# Deck_SchV1_1.net
KiCad netlist of a schematic drawn in Altium Designer
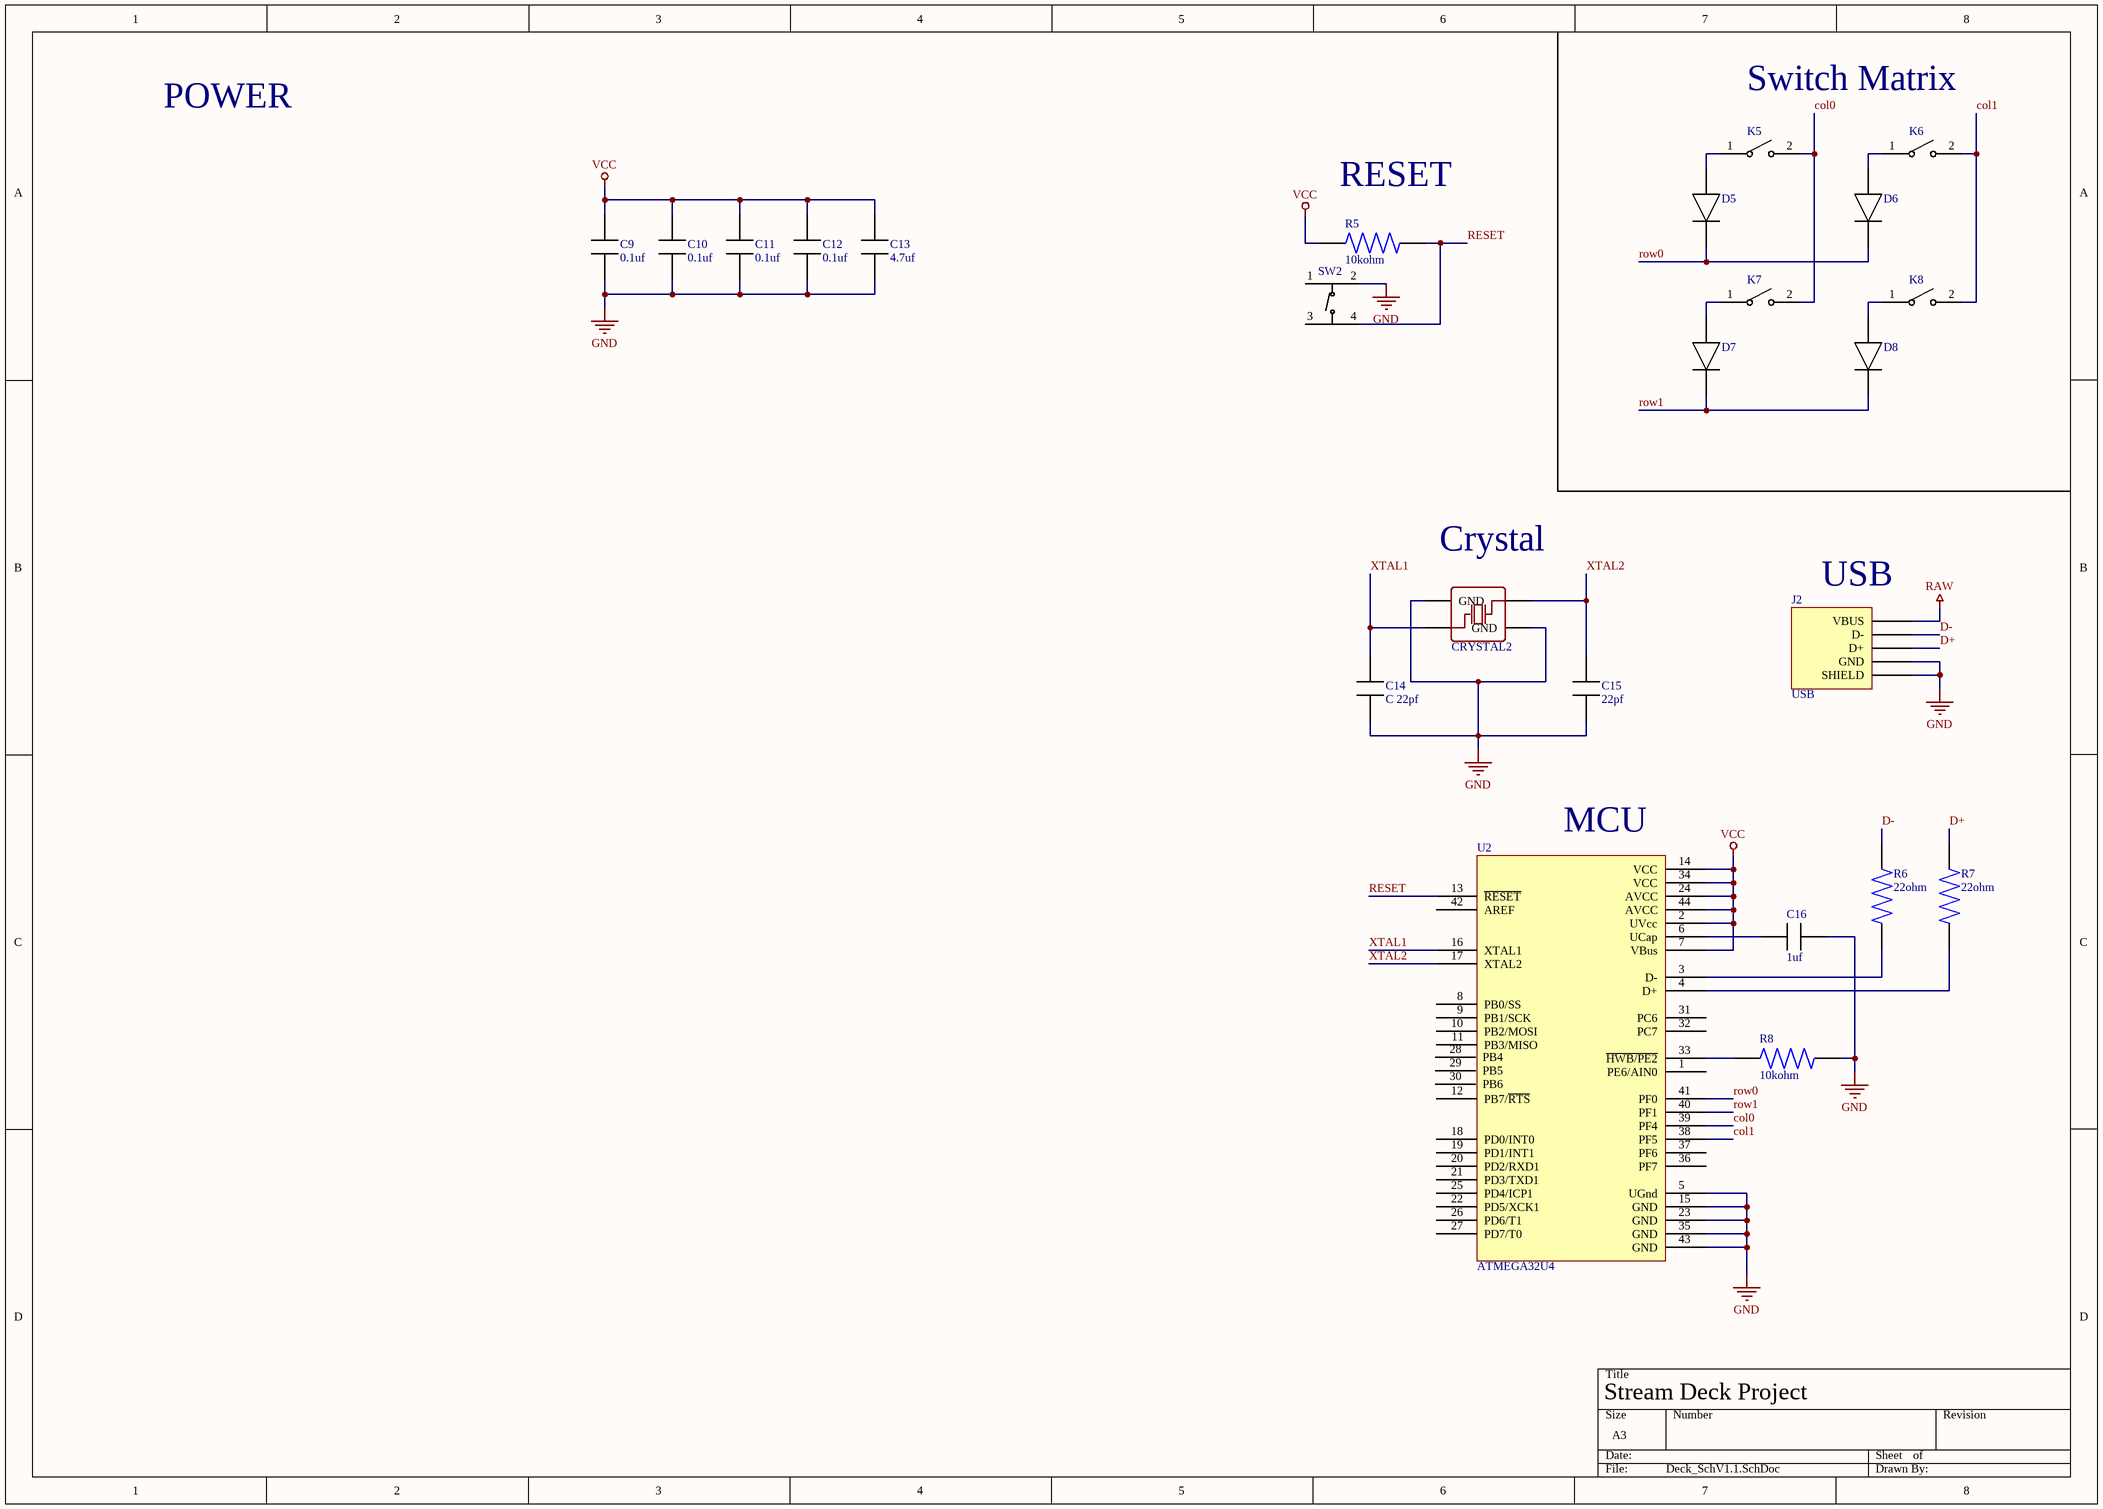
[diagram p0: Deck_SchV1.1.SchDoc]

(export (version "E")
  (design (tool "Eeschema 10.0.6"))
  (components
    (comp (ref "C9")
      (value "0.1uf")
      (footprint "C0805")
      (fields
        (field (name "MANUFACTURER") "Yageo")
        (field (name "MANUFACTURER PART NUMBER") "CC0805ZRY5V9BB104")
        (field (name "TOLERANCE") "80%")
      )
      (libsource (lib "Deck_SchlibV2") (part "CC0805ZRY5V9BB104"))
    )
    (comp (ref "C10")
      (value "0.1uf")
      (footprint "C0805")
      (fields
        (field (name "MANUFACTURER") "Yageo")
        (field (name "MANUFACTURER PART NUMBER") "CC0805ZRY5V9BB104")
        (field (name "TOLERANCE") "80%")
      )
      (libsource (lib "Deck_SchlibV2") (part "CC0805ZRY5V9BB104"))
    )
    (comp (ref "C11")
      (value "0.1uf")
      (footprint "C0805")
      (fields
        (field (name "MANUFACTURER") "Yageo")
        (field (name "MANUFACTURER PART NUMBER") "CC0805ZRY5V9BB104")
        (field (name "TOLERANCE") "80%")
      )
      (libsource (lib "Deck_SchlibV2") (part "CC0805ZRY5V9BB104"))
    )
    (comp (ref "C12")
      (value "0.1uf")
      (footprint "C0805")
      (fields
        (field (name "MANUFACTURER") "Yageo")
        (field (name "MANUFACTURER PART NUMBER") "CC0805ZRY5V9BB104")
        (field (name "TOLERANCE") "80%")
      )
      (libsource (lib "Deck_SchlibV2") (part "CC0805ZRY5V9BB104"))
    )
    (comp (ref "C13")
      (value "4.7uf")
      (footprint "C0805")
      (fields
        (field (name "MANUFACTURER") "Samsung")
        (field (name "MANUFACTURER PART NUMBER") "CL21A475KAQNNNE")
        (field (name "TOLERANCE") "10%")
      )
      (libsource (lib "Deck_SchlibV2") (part "CL21A475KAQNNNE"))
    )
    (comp (ref "C14")
      (value "C 22pf")
      (footprint "C0805")
      (description "Cap Ceramic 22pF 50V C0G 5% SMD 0805 125C T/R")
      (fields
        (field (name "MANUFACTURER") "Samsung")
        (field (name "MANUFACTURER PART NUMBER") "CL21C220JBANNNC")
      )
      (libsource (lib "Deck_SchlibV2") (part "CL21C220JBANNNC"))
    )
    (comp (ref "C15")
      (value "22pf")
      (footprint "C0805")
      (description "Cap Ceramic 22pF 50V C0G 5% SMD 0805 125C T/R")
      (fields
        (field (name "MANUFACTURER") "Samsung")
        (field (name "MANUFACTURER PART NUMBER") "CL21C220JBANNNC")
      )
      (libsource (lib "Deck_SchlibV2") (part "CL21C220JBANNNC"))
    )
    (comp (ref "C16")
      (value "1uf")
      (footprint "C0805")
      (fields
        (field (name "MANUFACTURER") "Samsung")
        (field (name "MANUFACTURER PART NUMBER") "CL21B105KBFNNNE")
        (field (name "TOLERANCE") "10%")
      )
      (libsource (lib "Deck_SchlibV2") (part "CL21B105KBFNNNE"))
    )
    (comp (ref "CRYSTAL2")
      (value "Crystal")
      (footprint "CRYSTAL-SMD_4P-L3.2-W2.5-BL")
      (fields (field (name "MANUFACTURER") "Seiko") (field (name "MANUFACTURER PART NUMBER") "X1E0000210264"))
      (libsource (lib "Deck_SchlibV2") (part "X1E0000210264"))
    )
    (comp (ref "D5")
      (value "Diode")
      (footprint "SOD-123_L2.8-W1.8-LS3.7-RD")
      (description "MICRO COMMERCIAL COMPONENTS - 1N4148W-TP - SWITCHING DIODE, 150mA, 100V, SOD123, FU")
      (fields (field (name "MANUFACTURER") "MCC") (field (name "MANUFACTURER PART NUMBER") "1N4148W-TP"))
      (libsource (lib "Deck_SchlibV2") (part "1N4148W-TP"))
    )
    (comp (ref "D6")
      (value "Diode")
      (footprint "SOD-123_L2.8-W1.8-LS3.7-RD")
      (description "MICRO COMMERCIAL COMPONENTS - 1N4148W-TP - SWITCHING DIODE, 150mA, 100V, SOD123, FU")
      (fields (field (name "MANUFACTURER") "MCC") (field (name "MANUFACTURER PART NUMBER") "1N4148W-TP"))
      (libsource (lib "Deck_SchlibV2") (part "1N4148W-TP"))
    )
    (comp (ref "D7")
      (value "Diode")
      (footprint "SOD-123_L2.8-W1.8-LS3.7-RD")
      (description "MICRO COMMERCIAL COMPONENTS - 1N4148W-TP - SWITCHING DIODE, 150mA, 100V, SOD123, FU")
      (fields (field (name "MANUFACTURER") "MCC") (field (name "MANUFACTURER PART NUMBER") "1N4148W-TP"))
      (libsource (lib "Deck_SchlibV2") (part "1N4148W-TP"))
    )
    (comp (ref "D8")
      (value "Diode")
      (footprint "SOD-123_L2.8-W1.8-LS3.7-RD")
      (description "MICRO COMMERCIAL COMPONENTS - 1N4148W-TP - SWITCHING DIODE, 150mA, 100V, SOD123, FU")
      (fields (field (name "MANUFACTURER") "MCC") (field (name "MANUFACTURER PART NUMBER") "1N4148W-TP"))
      (libsource (lib "Deck_SchlibV2") (part "1N4148W-TP"))
    )
    (comp (ref "J2")
      (value "USB")
      (footprint "USB")
      (description "Conn Mini USB 2.0 Type B RCP 5 POS 0.8mm Solder RA SMD 5 Terminal 1 Port Embossed T/R")
      (fields
        (field (name "MANUFACTURER") "Hirose")
        (field (name "MANUFACTURER PART NUMBER") "UX60SC-MB-5S8")
      )
      (libsource (lib "Deck_SchlibV2") (part "UX60SC-MB-5S8"))
    )
    (comp (ref "K5")
      (value "Switch")
      (footprint "Mx_Alps_100")
      (libsource (lib "Deck_SchlibV2") (part "Keyboard Switch"))
    )
    (comp (ref "K6")
      (value "Switch")
      (footprint "Mx_Alps_100")
      (libsource (lib "Deck_SchlibV2") (part "Keyboard Switch"))
    )
    (comp (ref "K7")
      (value "Switch")
      (footprint "Mx_Alps_100")
      (libsource (lib "Deck_SchlibV2") (part "Keyboard Switch"))
    )
    (comp (ref "K8")
      (value "Switch")
      (footprint "Mx_Alps_100")
      (libsource (lib "Deck_SchlibV2") (part "Keyboard Switch"))
    )
    (comp (ref "R5")
      (value "10kohm")
      (footprint "R0805")
      (fields
        (field (name "MANUFACTURER") "Uniroyal")
        (field (name "MANUFACTURER PART NUMBER") "0805W8F1002T5E")
      )
      (libsource (lib "Deck_SchlibV2") (part "0805W8F1002T5E"))
    )
    (comp (ref "R6")
      (value "22ohm")
      (footprint "R0805")
      (fields
        (field (name "MANUFACTURER") "Uniroyal")
        (field (name "MANUFACTURER PART NUMBER") "0805W8F220JT5E")
      )
      (libsource (lib "Deck_SchlibV2") (part "0805W8F220JT5E"))
    )
    (comp (ref "R7")
      (value "22ohm")
      (footprint "R0805")
      (fields
        (field (name "MANUFACTURER") "Uniroyal")
        (field (name "MANUFACTURER PART NUMBER") "0805W8F220JT5E")
      )
      (libsource (lib "Deck_SchlibV2") (part "0805W8F220JT5E"))
    )
    (comp (ref "R8")
      (value "10kohm")
      (footprint "R0805")
      (fields
        (field (name "MANUFACTURER") "Uniroyal")
        (field (name "MANUFACTURER PART NUMBER") "0805W8F1002T5E")
      )
      (libsource (lib "Deck_SchlibV2") (part "0805W8F1002T5E"))
    )
    (comp (ref "SW2")
      (value "Button")
      (footprint "SW-SMD_4P-L5.1-W5.1-P3.70-LS6.5-TL-2")
      (fields
        (field (name "MANUFACTURER") "XKB Connectivity")
        (field (name "MANUFACTURER PART NUMBER") "TS-1187A-B-A-B")
      )
      (libsource (lib "Deck_SchlibV2") (part "TS-1187A-B-A-B"))
    )
    (comp (ref "U2")
      (value "ATMEGA32U4")
      (footprint "ATMEGA32U2-AUR")
      (description "IC MCU 8BIT 32KB FLASH 32TQFP")
      (fields
        (field (name "MANUFACTURER") "Microchip / Atmel")
        (field (name "MANUFACTURER PART NUMBER") "ATMEGA32U2-AUR")
      )
      (libsource (lib "Deck_SchlibV2") (part "ATMEGA32U2-AUR"))
    )
  )
  (nets
    (net (code "1") (name "/D+") (class "Default")
      (node (ref "J2") (pin "3") (pinfunction "D+_3") (pintype "passive"))
      (node (ref "R7") (pin "57") (pinfunction "57_57") (pintype "passive"))
    )
    (net (code "2") (name "/D-") (class "Default")
      (node (ref "J2") (pin "2") (pinfunction "D-_2") (pintype "passive"))
      (node (ref "R6") (pin "57") (pinfunction "57_57") (pintype "passive"))
    )
    (net (code "3") (name "/RESET") (class "Default")
      (node (ref "R5") (pin "57") (pinfunction "57_57") (pintype "passive"))
      (node (ref "SW2") (pin "4") (pinfunction "D_4") (pintype "passive"))
      (node (ref "U2") (pin "13") (pinfunction "~{RESET}_13") (pintype "passive"))
    )
    (net (code "4") (name "/XTAL1") (class "Default")
      (node (ref "C14") (pin "54") (pinfunction "54_54") (pintype "passive"))
      (node (ref "CRYSTAL2") (pin "1") (pinfunction "OSC1_1") (pintype "passive"))
      (node (ref "U2") (pin "16") (pinfunction "XTAL1_16") (pintype "passive"))
    )
    (net (code "5") (name "/XTAL2") (class "Default")
      (node (ref "C15") (pin "54") (pinfunction "54_54") (pintype "passive"))
      (node (ref "CRYSTAL2") (pin "3") (pinfunction "OSC2_3") (pintype "passive"))
      (node (ref "U2") (pin "17") (pinfunction "XTAL2_17") (pintype "passive"))
    )
    (net (code "6") (name "/col0") (class "Default")
      (node (ref "K5") (pin "2") (pinfunction "2_2") (pintype "passive"))
      (node (ref "K7") (pin "2") (pinfunction "2_2") (pintype "passive"))
      (node (ref "U2") (pin "39") (pinfunction "PF4_39") (pintype "passive"))
    )
    (net (code "7") (name "/col1") (class "Default")
      (node (ref "K6") (pin "2") (pinfunction "2_2") (pintype "passive"))
      (node (ref "K8") (pin "2") (pinfunction "2_2") (pintype "passive"))
      (node (ref "U2") (pin "38") (pinfunction "PF5_38") (pintype "passive"))
    )
    (net (code "8") (name "/row0") (class "Default")
      (node (ref "D5") (pin "2") (pinfunction "-_2") (pintype "passive"))
      (node (ref "D6") (pin "2") (pinfunction "-_2") (pintype "passive"))
      (node (ref "U2") (pin "41") (pinfunction "PF0_41") (pintype "passive"))
    )
    (net (code "9") (name "/row1") (class "Default")
      (node (ref "D7") (pin "2") (pinfunction "-_2") (pintype "passive"))
      (node (ref "D8") (pin "2") (pinfunction "-_2") (pintype "passive"))
      (node (ref "U2") (pin "40") (pinfunction "PF1_40") (pintype "passive"))
    )
    (net (code "10") (name "GND") (class "Default")
      (node (ref "C10") (pin "55") (pinfunction "55_55") (pintype "passive"))
      (node (ref "C11") (pin "55") (pinfunction "55_55") (pintype "passive"))
      (node (ref "C12") (pin "55") (pinfunction "55_55") (pintype "passive"))
      (node (ref "C13") (pin "55") (pinfunction "55_55") (pintype "passive"))
      (node (ref "C14") (pin "55") (pinfunction "55_55") (pintype "passive"))
      (node (ref "C15") (pin "55") (pinfunction "55_55") (pintype "passive"))
      (node (ref "C16") (pin "55") (pinfunction "55_55") (pintype "passive"))
      (node (ref "C9") (pin "55") (pinfunction "55_55") (pintype "passive"))
      (node (ref "CRYSTAL2") (pin "2") (pinfunction "GND_2") (pintype "passive"))
      (node (ref "CRYSTAL2") (pin "4") (pinfunction "GND_4") (pintype "passive"))
      (node (ref "J2") (pin "4") (pinfunction "GND_4") (pintype "passive"))
      (node (ref "J2") (pin "5") (pinfunction "SHIELD_5") (pintype "passive"))
      (node (ref "R8") (pin "57") (pinfunction "57_57") (pintype "passive"))
      (node (ref "SW2") (pin "2") (pinfunction "B_2") (pintype "passive"))
      (node (ref "U2") (pin "15") (pinfunction "GND_15") (pintype "passive"))
      (node (ref "U2") (pin "23") (pinfunction "GND_23") (pintype "passive"))
      (node (ref "U2") (pin "35") (pinfunction "GND_35") (pintype "passive"))
      (node (ref "U2") (pin "43") (pinfunction "GND_43") (pintype "passive"))
      (node (ref "U2") (pin "5") (pinfunction "UGnd_5") (pintype "passive"))
    )
    (net (code "11") (name "Net-(D5-+)") (class "Default")
      (node (ref "D5") (pin "1") (pinfunction "+_1") (pintype "passive"))
      (node (ref "K5") (pin "1") (pinfunction "1_1") (pintype "passive"))
    )
    (net (code "12") (name "Net-(D6-+)") (class "Default")
      (node (ref "D6") (pin "1") (pinfunction "+_1") (pintype "passive"))
      (node (ref "K6") (pin "1") (pinfunction "1_1") (pintype "passive"))
    )
    (net (code "13") (name "Net-(D7-+)") (class "Default")
      (node (ref "D7") (pin "1") (pinfunction "+_1") (pintype "passive"))
      (node (ref "K7") (pin "1") (pinfunction "1_1") (pintype "passive"))
    )
    (net (code "14") (name "Net-(D8-+)") (class "Default")
      (node (ref "D8") (pin "1") (pinfunction "+_1") (pintype "passive"))
      (node (ref "K8") (pin "1") (pinfunction "1_1") (pintype "passive"))
    )
    (net (code "15") (name "Net-(U2-D+)") (class "Default")
      (node (ref "R7") (pin "56") (pinfunction "56_56") (pintype "passive"))
      (node (ref "U2") (pin "4") (pinfunction "D+_4") (pintype "passive"))
    )
    (net (code "16") (name "Net-(U2-D-)") (class "Default")
      (node (ref "R6") (pin "56") (pinfunction "56_56") (pintype "passive"))
      (node (ref "U2") (pin "3") (pinfunction "D-_3") (pintype "passive"))
    )
    (net (code "17") (name "Net-(U2-UCap)") (class "Default")
      (node (ref "C16") (pin "54") (pinfunction "54_54") (pintype "passive"))
      (node (ref "U2") (pin "6") (pinfunction "UCap_6") (pintype "passive"))
    )
    (net (code "18") (name "Net-(U2-~{HWB{slash}PE2})") (class "Default")
      (node (ref "R8") (pin "56") (pinfunction "56_56") (pintype "passive"))
      (node (ref "U2") (pin "33") (pinfunction "~{HWB/PE2}_33") (pintype "passive"))
    )
    (net (code "19") (name "RAW") (class "Default")
      (node (ref "J2") (pin "1") (pinfunction "VBUS_1") (pintype "passive"))
    )
    (net (code "20") (name "VCC") (class "Default")
      (node (ref "C10") (pin "54") (pinfunction "54_54") (pintype "passive"))
      (node (ref "C11") (pin "54") (pinfunction "54_54") (pintype "passive"))
      (node (ref "C12") (pin "54") (pinfunction "54_54") (pintype "passive"))
      (node (ref "C13") (pin "54") (pinfunction "54_54") (pintype "passive"))
      (node (ref "C9") (pin "54") (pinfunction "54_54") (pintype "passive"))
      (node (ref "R5") (pin "56") (pinfunction "56_56") (pintype "passive"))
      (node (ref "U2") (pin "14") (pinfunction "VCC_14") (pintype "passive"))
      (node (ref "U2") (pin "2") (pinfunction "UVcc_2") (pintype "passive"))
      (node (ref "U2") (pin "24") (pinfunction "AVCC_24") (pintype "passive"))
      (node (ref "U2") (pin "34") (pinfunction "VCC_34") (pintype "passive"))
      (node (ref "U2") (pin "44") (pinfunction "AVCC_44") (pintype "passive"))
      (node (ref "U2") (pin "7") (pinfunction "VBus_7") (pintype "passive"))
    )
    (net (code "21") (name "unconnected-(SW2-A-Pad1)") (class "Default")
      (node (ref "SW2") (pin "1") (pinfunction "A_1") (pintype "passive"))
    )
    (net (code "22") (name "unconnected-(SW2-C-Pad3)") (class "Default")
      (node (ref "SW2") (pin "3") (pinfunction "C_3") (pintype "passive"))
    )
    (net (code "23") (name "unconnected-(U2-AREF-Pad42)") (class "Default")
      (node (ref "U2") (pin "42") (pinfunction "AREF_42") (pintype "passive"))
    )
    (net (code "24") (name "unconnected-(U2-PB0{slash}SS-Pad8)") (class "Default")
      (node (ref "U2") (pin "8") (pinfunction "PB0/SS_8") (pintype "passive"))
    )
    (net (code "25") (name "unconnected-(U2-PB1{slash}SCK-Pad9)") (class "Default")
      (node (ref "U2") (pin "9") (pinfunction "PB1/SCK_9") (pintype "passive"))
    )
    (net (code "26") (name "unconnected-(U2-PB2{slash}MOSI-Pad10)") (class "Default")
      (node (ref "U2") (pin "10") (pinfunction "PB2/MOSI_10") (pintype "passive"))
    )
    (net (code "27") (name "unconnected-(U2-PB3{slash}MISO-Pad11)") (class "Default")
      (node (ref "U2") (pin "11") (pinfunction "PB3/MISO_11") (pintype "passive"))
    )
    (net (code "28") (name "unconnected-(U2-PB4-Pad28)") (class "Default")
      (node (ref "U2") (pin "28") (pinfunction "PB4_28") (pintype "passive"))
    )
    (net (code "29") (name "unconnected-(U2-PB5-Pad29)") (class "Default")
      (node (ref "U2") (pin "29") (pinfunction "PB5_29") (pintype "passive"))
    )
    (net (code "30") (name "unconnected-(U2-PB6-Pad30)") (class "Default")
      (node (ref "U2") (pin "30") (pinfunction "PB6_30") (pintype "passive"))
    )
    (net (code "31") (name "unconnected-(U2-PB7{slash}~{RTS}-Pad12)") (class "Default")
      (node (ref "U2") (pin "12") (pinfunction "PB7/~{RTS}_12") (pintype "passive"))
    )
    (net (code "32") (name "unconnected-(U2-PC6-Pad31)") (class "Default")
      (node (ref "U2") (pin "31") (pinfunction "PC6_31") (pintype "passive"))
    )
    (net (code "33") (name "unconnected-(U2-PC7-Pad32)") (class "Default")
      (node (ref "U2") (pin "32") (pinfunction "PC7_32") (pintype "passive"))
    )
    (net (code "34") (name "unconnected-(U2-PD0{slash}INT0-Pad18)") (class "Default")
      (node (ref "U2") (pin "18") (pinfunction "PD0/INT0_18") (pintype "passive"))
    )
    (net (code "35") (name "unconnected-(U2-PD1{slash}INT1-Pad19)") (class "Default")
      (node (ref "U2") (pin "19") (pinfunction "PD1/INT1_19") (pintype "passive"))
    )
    (net (code "36") (name "unconnected-(U2-PD2{slash}RXD1-Pad20)") (class "Default")
      (node (ref "U2") (pin "20") (pinfunction "PD2/RXD1_20") (pintype "passive"))
    )
    (net (code "37") (name "unconnected-(U2-PD3{slash}TXD1-Pad21)") (class "Default")
      (node (ref "U2") (pin "21") (pinfunction "PD3/TXD1_21") (pintype "passive"))
    )
    (net (code "38") (name "unconnected-(U2-PD4{slash}ICP1-Pad25)") (class "Default")
      (node (ref "U2") (pin "25") (pinfunction "PD4/ICP1_25") (pintype "passive"))
    )
    (net (code "39") (name "unconnected-(U2-PD5{slash}XCK1-Pad22)") (class "Default")
      (node (ref "U2") (pin "22") (pinfunction "PD5/XCK1_22") (pintype "passive"))
    )
    (net (code "40") (name "unconnected-(U2-PD6{slash}T1-Pad26)") (class "Default")
      (node (ref "U2") (pin "26") (pinfunction "PD6/T1_26") (pintype "passive"))
    )
    (net (code "41") (name "unconnected-(U2-PD7{slash}T0-Pad27)") (class "Default")
      (node (ref "U2") (pin "27") (pinfunction "PD7/T0_27") (pintype "passive"))
    )
    (net (code "42") (name "unconnected-(U2-PE6{slash}AIN0-Pad1)") (class "Default")
      (node (ref "U2") (pin "1") (pinfunction "PE6/AIN0_1") (pintype "passive"))
    )
    (net (code "43") (name "unconnected-(U2-PF6-Pad37)") (class "Default")
      (node (ref "U2") (pin "37") (pinfunction "PF6_37") (pintype "passive"))
    )
    (net (code "44") (name "unconnected-(U2-PF7-Pad36)") (class "Default")
      (node (ref "U2") (pin "36") (pinfunction "PF7_36") (pintype "passive"))
    )
  )
)
